# Sheet06.net
KiCad netlist of a schematic drawn in Altium Designer
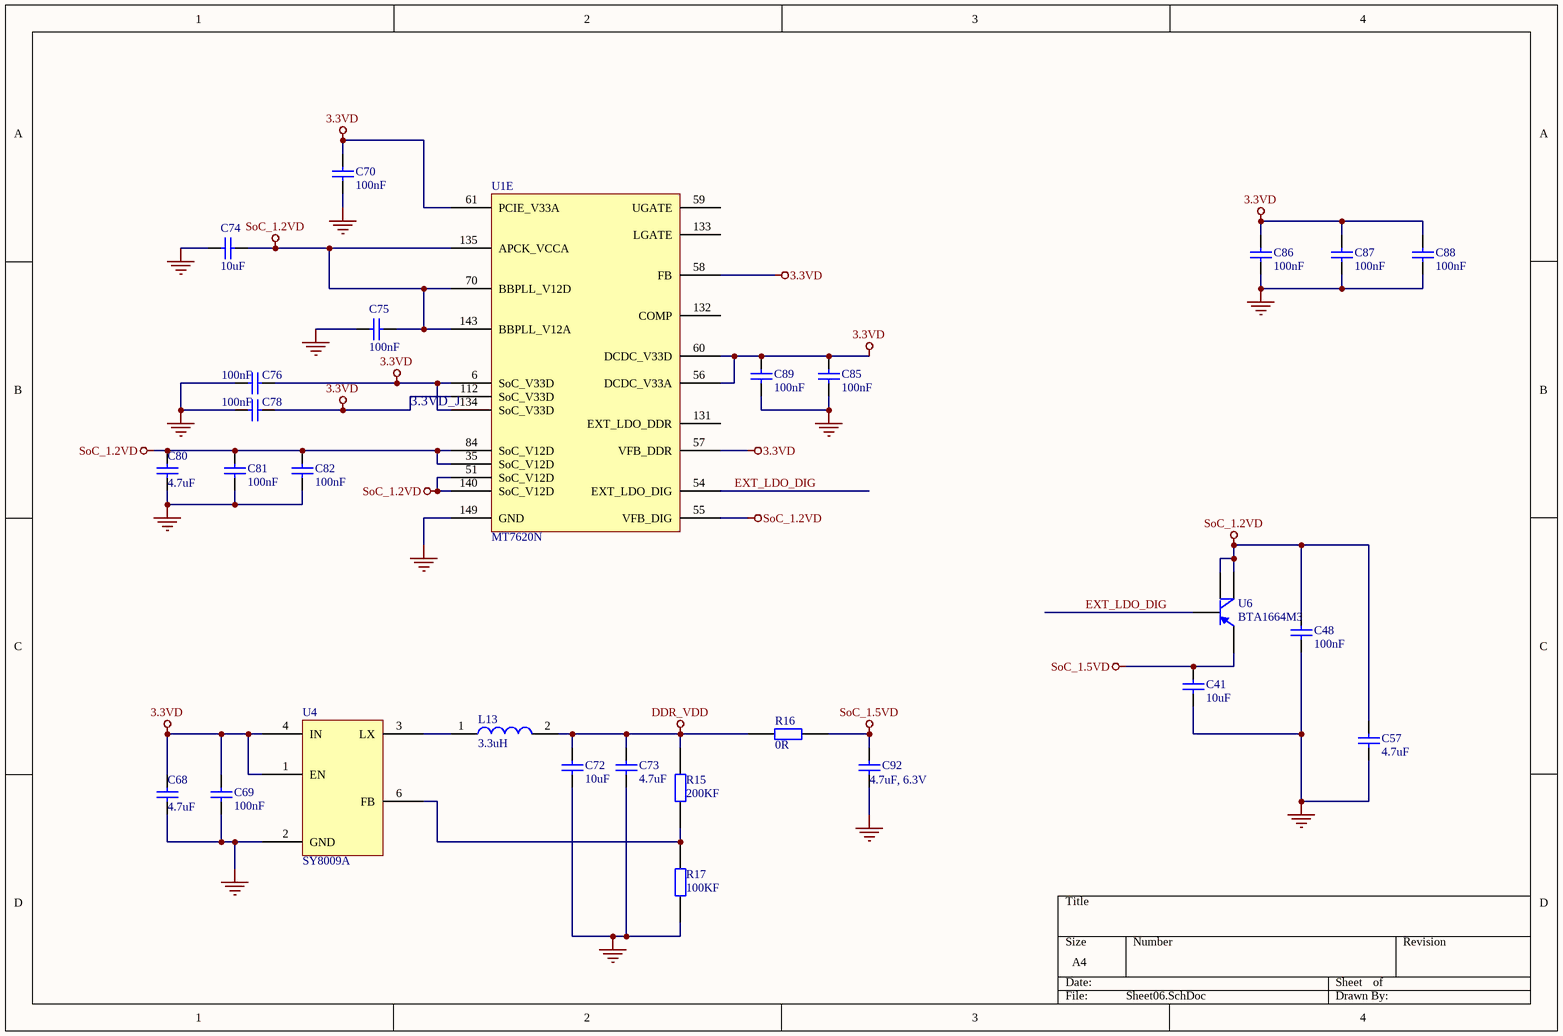
[diagram p0: Sheet06.SchDoc]

(export (version "E")
  (design (tool "Eeschema 10.0.6"))
  (components
    (comp (ref "C41")
      (value "10uF")
      (footprint "R0805")
      (description "Capacitor (Semiconductor SIM Model)")
      (fields
        (field (name "MANUFACTURER") "Generic Components")
        (field (name "PUBLISHER") "Altium Hobart Technology Centre")
      )
      (libsource (lib "myschlib") (part "Cap Semi"))
    )
    (comp (ref "C48")
      (value "100nF")
      (footprint "R0402")
      (description "Capacitor (Semiconductor SIM Model)")
      (fields
        (field (name "MANUFACTURER") "Generic Components")
        (field (name "PUBLISHER") "Altium Hobart Technology Centre")
      )
      (libsource (lib "myschlib") (part "Cap Semi"))
    )
    (comp (ref "C57")
      (value "4.7uF")
      (footprint "R0603")
      (description "Capacitor (Semiconductor SIM Model)")
      (fields
        (field (name "MANUFACTURER") "Generic Components")
        (field (name "PUBLISHER") "Altium Hobart Technology Centre")
      )
      (libsource (lib "myschlib") (part "Cap Semi"))
    )
    (comp (ref "C68")
      (value "4.7uF")
      (footprint "R0603")
      (description "2pF, 50V, +/-0.25pF")
      (fields
        (field (name "MANUFACTURER") "Generic Components")
        (field (name "PUBLISHER") "Altium Hobart Technology Centre")
      )
      (libsource (lib "myschlib") (part "Cap Semi"))
    )
    (comp (ref "C69")
      (value "100nF")
      (footprint "R0402")
      (description "2pF, 50V, +/-0.25pF")
      (fields
        (field (name "MANUFACTURER") "Generic Components")
        (field (name "PUBLISHER") "Altium Hobart Technology Centre")
      )
      (libsource (lib "myschlib") (part "Cap Semi"))
    )
    (comp (ref "C70")
      (value "100nF")
      (footprint "R0402")
      (description "2pF, 50V, +/-0.25pF")
      (fields
        (field (name "MANUFACTURER") "Generic Components")
        (field (name "PUBLISHER") "Altium Hobart Technology Centre")
      )
      (libsource (lib "myschlib") (part "Cap Semi"))
    )
    (comp (ref "C72")
      (value "10uF")
      (footprint "R0805")
      (description "2pF, 50V, +/-0.25pF")
      (fields
        (field (name "MANUFACTURER") "Generic Components")
        (field (name "PUBLISHER") "Altium Hobart Technology Centre")
      )
      (libsource (lib "myschlib") (part "Cap Semi"))
    )
    (comp (ref "C73")
      (value "4.7uF")
      (footprint "R0603")
      (description "2pF, 50V, +/-0.25pF")
      (fields
        (field (name "MANUFACTURER") "Generic Components")
        (field (name "PUBLISHER") "Altium Hobart Technology Centre")
      )
      (libsource (lib "myschlib") (part "Cap Semi"))
    )
    (comp (ref "C74")
      (value "10uF")
      (footprint "R0805")
      (description "2pF, 50V, +/-0.25pF")
      (fields
        (field (name "MANUFACTURER") "Generic Components")
        (field (name "PUBLISHER") "Altium Hobart Technology Centre")
      )
      (libsource (lib "myschlib") (part "Cap Semi"))
    )
    (comp (ref "C75")
      (value "100nF")
      (footprint "R0402")
      (description "2pF, 50V, +/-0.25pF")
      (fields
        (field (name "MANUFACTURER") "Generic Components")
        (field (name "PUBLISHER") "Altium Hobart Technology Centre")
      )
      (libsource (lib "myschlib") (part "Cap Semi"))
    )
    (comp (ref "C76")
      (value "100nF")
      (footprint "R0402")
      (description "2pF, 50V, +/-0.25pF")
      (fields
        (field (name "MANUFACTURER") "Generic Components")
        (field (name "PUBLISHER") "Altium Hobart Technology Centre")
      )
      (libsource (lib "myschlib") (part "Cap Semi"))
    )
    (comp (ref "C78")
      (value "100nF")
      (footprint "R0402")
      (description "2pF, 50V, +/-0.25pF")
      (fields
        (field (name "MANUFACTURER") "Generic Components")
        (field (name "PUBLISHER") "Altium Hobart Technology Centre")
      )
      (libsource (lib "myschlib") (part "Cap Semi"))
    )
    (comp (ref "C80")
      (value "4.7uF")
      (footprint "R0603")
      (description "2pF, 50V, +/-0.25pF")
      (fields
        (field (name "MANUFACTURER") "Generic Components")
        (field (name "PUBLISHER") "Altium Hobart Technology Centre")
      )
      (libsource (lib "myschlib") (part "Cap Semi"))
    )
    (comp (ref "C81")
      (value "100nF")
      (footprint "R0402")
      (description "2pF, 50V, +/-0.25pF")
      (fields
        (field (name "MANUFACTURER") "Generic Components")
        (field (name "PUBLISHER") "Altium Hobart Technology Centre")
      )
      (libsource (lib "myschlib") (part "Cap Semi"))
    )
    (comp (ref "C82")
      (value "100nF")
      (footprint "R0402")
      (description "2pF, 50V, +/-0.25pF")
      (fields
        (field (name "MANUFACTURER") "Generic Components")
        (field (name "PUBLISHER") "Altium Hobart Technology Centre")
      )
      (libsource (lib "myschlib") (part "Cap Semi"))
    )
    (comp (ref "C85")
      (value "100nF")
      (footprint "R0402")
      (description "2pF, 50V, +/-0.25pF")
      (fields
        (field (name "MANUFACTURER") "Generic Components")
        (field (name "PUBLISHER") "Altium Hobart Technology Centre")
      )
      (libsource (lib "myschlib") (part "Cap Semi"))
    )
    (comp (ref "C86")
      (value "100nF")
      (footprint "R0402")
      (description "2pF, 50V, +/-0.25pF")
      (fields
        (field (name "MANUFACTURER") "Generic Components")
        (field (name "PUBLISHER") "Altium Hobart Technology Centre")
      )
      (libsource (lib "myschlib") (part "Cap Semi"))
    )
    (comp (ref "C87")
      (value "100nF")
      (footprint "R0402")
      (description "2pF, 50V, +/-0.25pF")
      (fields
        (field (name "MANUFACTURER") "Generic Components")
        (field (name "PUBLISHER") "Altium Hobart Technology Centre")
      )
      (libsource (lib "myschlib") (part "Cap Semi"))
    )
    (comp (ref "C88")
      (value "100nF")
      (footprint "R0402")
      (description "2pF, 50V, +/-0.25pF")
      (fields
        (field (name "MANUFACTURER") "Generic Components")
        (field (name "PUBLISHER") "Altium Hobart Technology Centre")
      )
      (libsource (lib "myschlib") (part "Cap Semi"))
    )
    (comp (ref "C89")
      (value "100nF")
      (footprint "R0402")
      (description "2pF, 50V, +/-0.25pF")
      (fields
        (field (name "MANUFACTURER") "Generic Components")
        (field (name "PUBLISHER") "Altium Hobart Technology Centre")
      )
      (libsource (lib "myschlib") (part "Cap Semi"))
    )
    (comp (ref "C92")
      (value "4.7uF, 6.3V")
      (footprint "R0603")
      (description "Capacitor (Semiconductor SIM Model)")
      (fields
        (field (name "MANUFACTURER") "Generic Components")
        (field (name "PUBLISHER") "Altium Hobart Technology Centre")
      )
      (libsource (lib "myschlib") (part "Cap Semi"))
    )
    (comp (ref "L13")
      (value "3.3uH")
      (footprint "LSMD3_8x3_8")
      (libsource (lib "myschlib") (part "INDUCTOR"))
    )
    (comp (ref "R15") (value "200KF") (footprint "R0402") (libsource (lib "") (part "RES_1")))
    (comp (ref "R16") (value "0R") (footprint "R1206") (libsource (lib "myschlib") (part "RES")))
    (comp (ref "R17") (value "100KF") (footprint "R0402") (libsource (lib "") (part "RES_1")))
    (comp (ref "U1") (value "MT7620N") (footprint "QFN-148-RT") (libsource (lib "myschlib") (part "MT7620N")))
    (comp (ref "U4") (value "SY8009A") (footprint "SOT23-6L") (libsource (lib "myschlib") (part "SY8008C")))
    (comp (ref "U6") (value "BTA1664M3") (footprint "SOT-89") (libsource (lib "myschlib") (part "BTA1664M3")))
  )
  (nets
    (net (code "1") (name "/EXT_LDO_DIG") (class "Default")
      (node (ref "U1") (pin "54") (pinfunction "EXT_LDO_DIG_54") (pintype "passive"))
      (node (ref "U6") (pin "1") (pinfunction "B_1") (pintype "passive"))
    )
    (net (code "2") (name "3.3VD") (class "Default")
      (node (ref "C68") (pin "2") (pinfunction "2_2") (pintype "passive"))
      (node (ref "C69") (pin "1") (pinfunction "1_1") (pintype "passive"))
      (node (ref "C70") (pin "1") (pinfunction "1_1") (pintype "passive"))
      (node (ref "C76") (pin "1") (pinfunction "1_1") (pintype "passive"))
      (node (ref "C78") (pin "1") (pinfunction "1_1") (pintype "passive"))
      (node (ref "C85") (pin "1") (pinfunction "1_1") (pintype "passive"))
      (node (ref "C86") (pin "1") (pinfunction "1_1") (pintype "passive"))
      (node (ref "C87") (pin "1") (pinfunction "1_1") (pintype "passive"))
      (node (ref "C88") (pin "1") (pinfunction "1_1") (pintype "passive"))
      (node (ref "C89") (pin "1") (pinfunction "1_1") (pintype "passive"))
      (node (ref "U1") (pin "112") (pinfunction "SoC_V33D_112") (pintype "passive"))
      (node (ref "U1") (pin "134") (pinfunction "SoC_V33D_134") (pintype "passive"))
      (node (ref "U1") (pin "56") (pinfunction "DCDC_V33A_56") (pintype "passive"))
      (node (ref "U1") (pin "57") (pinfunction "VFB_DDR_57") (pintype "passive"))
      (node (ref "U1") (pin "58") (pinfunction "FB_58") (pintype "passive"))
      (node (ref "U1") (pin "6") (pinfunction "SoC_V33D_6") (pintype "passive"))
      (node (ref "U1") (pin "60") (pinfunction "DCDC_V33D_60") (pintype "passive"))
      (node (ref "U1") (pin "61") (pinfunction "PCIE_V33A_61") (pintype "passive"))
      (node (ref "U4") (pin "1") (pinfunction "EN_1") (pintype "passive"))
      (node (ref "U4") (pin "4") (pinfunction "IN_4") (pintype "passive"))
    )
    (net (code "3") (name "DDR_VDD") (class "Default")
      (node (ref "C72") (pin "1") (pinfunction "1_1") (pintype "passive"))
      (node (ref "C73") (pin "1") (pinfunction "1_1") (pintype "passive"))
      (node (ref "L13") (pin "2") (pinfunction "2_2") (pintype "passive"))
      (node (ref "R15") (pin "1") (pinfunction "1_1") (pintype "passive"))
      (node (ref "R16") (pin "1") (pinfunction "1_1") (pintype "passive"))
    )
    (net (code "4") (name "GND") (class "Default")
      (node (ref "C41") (pin "2") (pinfunction "2_2") (pintype "passive"))
      (node (ref "C48") (pin "2") (pinfunction "2_2") (pintype "passive"))
      (node (ref "C57") (pin "2") (pinfunction "2_2") (pintype "passive"))
      (node (ref "C68") (pin "1") (pinfunction "1_1") (pintype "passive"))
      (node (ref "C69") (pin "2") (pinfunction "2_2") (pintype "passive"))
      (node (ref "C70") (pin "2") (pinfunction "2_2") (pintype "passive"))
      (node (ref "C72") (pin "2") (pinfunction "2_2") (pintype "passive"))
      (node (ref "C73") (pin "2") (pinfunction "2_2") (pintype "passive"))
      (node (ref "C74") (pin "2") (pinfunction "2_2") (pintype "passive"))
      (node (ref "C75") (pin "1") (pinfunction "1_1") (pintype "passive"))
      (node (ref "C76") (pin "2") (pinfunction "2_2") (pintype "passive"))
      (node (ref "C78") (pin "2") (pinfunction "2_2") (pintype "passive"))
      (node (ref "C80") (pin "1") (pinfunction "1_1") (pintype "passive"))
      (node (ref "C81") (pin "2") (pinfunction "2_2") (pintype "passive"))
      (node (ref "C82") (pin "2") (pinfunction "2_2") (pintype "passive"))
      (node (ref "C85") (pin "2") (pinfunction "2_2") (pintype "passive"))
      (node (ref "C86") (pin "2") (pinfunction "2_2") (pintype "passive"))
      (node (ref "C87") (pin "2") (pinfunction "2_2") (pintype "passive"))
      (node (ref "C88") (pin "2") (pinfunction "2_2") (pintype "passive"))
      (node (ref "C89") (pin "2") (pinfunction "2_2") (pintype "passive"))
      (node (ref "C92") (pin "1") (pinfunction "1_1") (pintype "passive"))
      (node (ref "R17") (pin "2") (pinfunction "2_2") (pintype "passive"))
      (node (ref "U1") (pin "149") (pinfunction "GND_149") (pintype "passive"))
      (node (ref "U4") (pin "2") (pinfunction "GND_2") (pintype "passive"))
    )
    (net (code "5") (name "Net-(U4-FB)") (class "Default")
      (node (ref "R15") (pin "2") (pinfunction "2_2") (pintype "passive"))
      (node (ref "R17") (pin "1") (pinfunction "1_1") (pintype "passive"))
      (node (ref "U4") (pin "6") (pinfunction "FB_6") (pintype "passive"))
    )
    (net (code "6") (name "Net-(U4-LX)") (class "Default")
      (node (ref "L13") (pin "1") (pinfunction "1_1") (pintype "passive"))
      (node (ref "U4") (pin "3") (pinfunction "LX_3") (pintype "passive"))
    )
    (net (code "7") (name "SoC_1.2VD") (class "Default")
      (node (ref "C48") (pin "1") (pinfunction "1_1") (pintype "passive"))
      (node (ref "C57") (pin "1") (pinfunction "1_1") (pintype "passive"))
      (node (ref "C74") (pin "1") (pinfunction "1_1") (pintype "passive"))
      (node (ref "C75") (pin "2") (pinfunction "2_2") (pintype "passive"))
      (node (ref "C80") (pin "2") (pinfunction "2_2") (pintype "passive"))
      (node (ref "C81") (pin "1") (pinfunction "1_1") (pintype "passive"))
      (node (ref "C82") (pin "1") (pinfunction "1_1") (pintype "passive"))
      (node (ref "U1") (pin "135") (pinfunction "APCK_VCCA_135") (pintype "passive"))
      (node (ref "U1") (pin "140") (pinfunction "SoC_V12D_140") (pintype "passive"))
      (node (ref "U1") (pin "143") (pinfunction "BBPLL_V12A_143") (pintype "passive"))
      (node (ref "U1") (pin "35") (pinfunction "SoC_V12D_35") (pintype "passive"))
      (node (ref "U1") (pin "51") (pinfunction "SoC_V12D_51") (pintype "passive"))
      (node (ref "U1") (pin "55") (pinfunction "VFB_DIG_55") (pintype "passive"))
      (node (ref "U1") (pin "70") (pinfunction "BBPLL_V12D_70") (pintype "passive"))
      (node (ref "U1") (pin "84") (pinfunction "SoC_V12D_84") (pintype "passive"))
      (node (ref "U6") (pin "2") (pinfunction "C_2") (pintype "passive"))
      (node (ref "U6") (pin "4") (pinfunction "C_4") (pintype "passive"))
    )
    (net (code "8") (name "SoC_1.5VD") (class "Default")
      (node (ref "C41") (pin "1") (pinfunction "1_1") (pintype "passive"))
      (node (ref "C92") (pin "2") (pinfunction "2_2") (pintype "passive"))
      (node (ref "R16") (pin "2") (pinfunction "2_2") (pintype "passive"))
      (node (ref "U6") (pin "3") (pinfunction "E_3") (pintype "passive"))
    )
    (net (code "9") (name "unconnected-(U1E-COMP-Pad132)") (class "Default")
      (node (ref "U1") (pin "132") (pinfunction "COMP_132") (pintype "passive"))
    )
    (net (code "10") (name "unconnected-(U1E-EXT_LDO_DDR-Pad131)") (class "Default")
      (node (ref "U1") (pin "131") (pinfunction "EXT_LDO_DDR_131") (pintype "passive"))
    )
    (net (code "11") (name "unconnected-(U1E-LGATE-Pad133)") (class "Default")
      (node (ref "U1") (pin "133") (pinfunction "LGATE_133") (pintype "passive"))
    )
    (net (code "12") (name "unconnected-(U1E-UGATE-Pad59)") (class "Default")
      (node (ref "U1") (pin "59") (pinfunction "UGATE_59") (pintype "passive"))
    )
  )
)
